# MOD1600.net
KiCad netlist of a schematic drawn in EAGLE
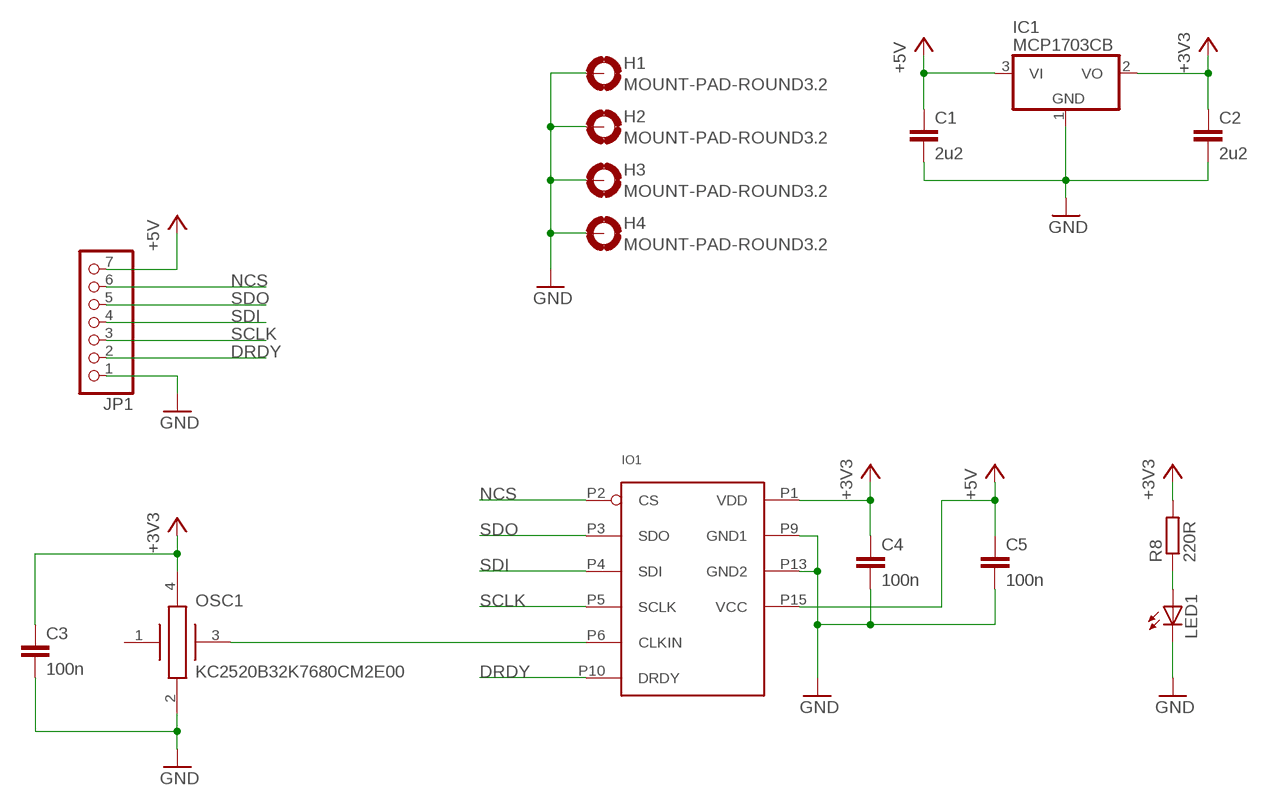
[diagram p0: schematic, sheet 1]

(export (version "E")
  (design (tool "Eeschema 10.0.6"))
  (components
    (comp (ref "C1")
      (value "2u2")
      (footprint "eagle-import:C0603")
      (libsource (lib "eagle-import") (part "C-EUC0603"))
    )
    (comp (ref "C2")
      (value "2u2")
      (footprint "eagle-import:C0603")
      (libsource (lib "eagle-import") (part "C-EUC0603"))
    )
    (comp (ref "C3")
      (value "100n")
      (footprint "eagle-import:C0603")
      (libsource (lib "eagle-import") (part "C-EUC0603"))
    )
    (comp (ref "C4")
      (value "100n")
      (footprint "eagle-import:C0603")
      (libsource (lib "eagle-import") (part "C-EUC0603"))
    )
    (comp (ref "C5")
      (value "100n")
      (footprint "eagle-import:C0603")
      (libsource (lib "eagle-import") (part "C-EUC0603"))
    )
    (comp (ref "H1")
      (value "MOUNT-PAD-ROUND3.2")
      (footprint "eagle-import:3,2-PAD")
      (libsource (lib "eagle-import") (part "MOUNT-PAD-ROUND3.2"))
    )
    (comp (ref "H2")
      (value "MOUNT-PAD-ROUND3.2")
      (footprint "eagle-import:3,2-PAD")
      (libsource (lib "eagle-import") (part "MOUNT-PAD-ROUND3.2"))
    )
    (comp (ref "H3")
      (value "MOUNT-PAD-ROUND3.2")
      (footprint "eagle-import:3,2-PAD")
      (libsource (lib "eagle-import") (part "MOUNT-PAD-ROUND3.2"))
    )
    (comp (ref "H4")
      (value "MOUNT-PAD-ROUND3.2")
      (footprint "eagle-import:3,2-PAD")
      (libsource (lib "eagle-import") (part "MOUNT-PAD-ROUND3.2"))
    )
    (comp (ref "IC1")
      (value "MCP1703CB")
      (footprint "eagle-import:SOT23")
      (libsource (lib "eagle-import") (part "MCP1703CB"))
    )
    (comp (ref "IO1")
      (value "MOD1600")
      (footprint "eagle-import:LGA_MOD1600")
      (libsource (lib "eagle-import") (part "MOD1600"))
    )
    (comp (ref "JP1")
      (value "PINHD-1X7/90")
      (footprint "eagle-import:1X07_90")
      (libsource (lib "eagle-import") (part "PINHD-1X7/90"))
    )
    (comp (ref "LED1")
      (value "LEDSML0603")
      (footprint "eagle-import:SML0603")
      (libsource (lib "eagle-import") (part "LEDSML0603"))
    )
    (comp (ref "OSC1")
      (value "KC2520B32K7680CM2E00")
      (footprint "eagle-import:SMD_OSC")
      (libsource (lib "eagle-import") (part "KC2520B"))
    )
    (comp (ref "R8")
      (value "220R")
      (footprint "eagle-import:R0603")
      (libsource (lib "eagle-import") (part "R-EU_R0603"))
    )
  )
  (nets
    (net (code "1") (name "+3V3") (class "Default")
      (node (ref "C2") (pin "1") (pinfunction "1_1") (pintype "passive"))
      (node (ref "C3") (pin "1") (pinfunction "1_1") (pintype "passive"))
      (node (ref "C4") (pin "1") (pinfunction "1_1") (pintype "passive"))
      (node (ref "IC1") (pin "2") (pinfunction "VO_2") (pintype "passive"))
      (node (ref "IO1") (pin "P1") (pinfunction "VDD_P1") (pintype "power_in"))
      (node (ref "OSC1") (pin "4") (pinfunction "VDD_4") (pintype "power_in"))
      (node (ref "R8") (pin "2") (pinfunction "2_2") (pintype "passive"))
    )
    (net (code "2") (name "+5V") (class "Default")
      (node (ref "C1") (pin "1") (pinfunction "1_1") (pintype "passive"))
      (node (ref "C5") (pin "1") (pinfunction "1_1") (pintype "passive"))
      (node (ref "IC1") (pin "3") (pinfunction "VI_3") (pintype "input"))
      (node (ref "IO1") (pin "P15") (pinfunction "VCC_P15") (pintype "power_in"))
      (node (ref "JP1") (pin "7") (pinfunction "7_7") (pintype "passive"))
    )
    (net (code "3") (name "/DRDY") (class "Default")
      (node (ref "IO1") (pin "P10") (pinfunction "DRDY_P10") (pintype "output"))
      (node (ref "JP1") (pin "2") (pinfunction "2_2") (pintype "passive"))
    )
    (net (code "4") (name "/NCS") (class "Default")
      (node (ref "IO1") (pin "P2") (pinfunction "CS_P2") (pintype "input"))
      (node (ref "JP1") (pin "6") (pinfunction "6_6") (pintype "passive"))
    )
    (net (code "5") (name "/SCLK") (class "Default")
      (node (ref "IO1") (pin "P5") (pinfunction "SCLK_P5") (pintype "output"))
      (node (ref "JP1") (pin "3") (pinfunction "3_3") (pintype "passive"))
    )
    (net (code "6") (name "/SDI") (class "Default")
      (node (ref "IO1") (pin "P4") (pinfunction "SDI_P4") (pintype "input"))
      (node (ref "JP1") (pin "4") (pinfunction "4_4") (pintype "passive"))
    )
    (net (code "7") (name "/SDO") (class "Default")
      (node (ref "IO1") (pin "P3") (pinfunction "SDO_P3") (pintype "output"))
      (node (ref "JP1") (pin "5") (pinfunction "5_5") (pintype "passive"))
    )
    (net (code "8") (name "GND") (class "Default")
      (node (ref "C1") (pin "2") (pinfunction "2_2") (pintype "passive"))
      (node (ref "C2") (pin "2") (pinfunction "2_2") (pintype "passive"))
      (node (ref "C3") (pin "2") (pinfunction "2_2") (pintype "passive"))
      (node (ref "C4") (pin "2") (pinfunction "2_2") (pintype "passive"))
      (node (ref "C5") (pin "2") (pinfunction "2_2") (pintype "passive"))
      (node (ref "H1") (pin "B3,2") (pinfunction "MOUNT_B3,2") (pintype "passive"))
      (node (ref "H2") (pin "B3,2") (pinfunction "MOUNT_B3,2") (pintype "passive"))
      (node (ref "H3") (pin "B3,2") (pinfunction "MOUNT_B3,2") (pintype "passive"))
      (node (ref "H4") (pin "B3,2") (pinfunction "MOUNT_B3,2") (pintype "passive"))
      (node (ref "IC1") (pin "1") (pinfunction "GND_1") (pintype "passive"))
      (node (ref "IO1") (pin "P13") (pinfunction "GND2_P13") (pintype "power_in"))
      (node (ref "IO1") (pin "P9") (pinfunction "GND1_P9") (pintype "power_in"))
      (node (ref "JP1") (pin "1") (pinfunction "1_1") (pintype "passive"))
      (node (ref "LED1") (pin "C") (pinfunction "C_C") (pintype "passive"))
      (node (ref "OSC1") (pin "2") (pinfunction "GND_2") (pintype "power_in"))
    )
    (net (code "9") (name "Net-(IO1-CLKIN)") (class "Default")
      (node (ref "IO1") (pin "P6") (pinfunction "CLKIN_P6") (pintype "input"))
      (node (ref "OSC1") (pin "3") (pinfunction "OUT_3") (pintype "output"))
    )
    (net (code "10") (name "Net-(LED1-PadA)") (class "Default")
      (node (ref "LED1") (pin "A") (pinfunction "A_A") (pintype "passive"))
      (node (ref "R8") (pin "1") (pinfunction "1_1") (pintype "passive"))
    )
    (net (code "11") (name "unconnected-(OSC1-INH-Pad1)") (class "Default")
      (node (ref "OSC1") (pin "1") (pinfunction "INH_1") (pintype "input"))
    )
  )
)
